# Laser_Teensy4.net
KiCad netlist of a schematic drawn in EAGLE
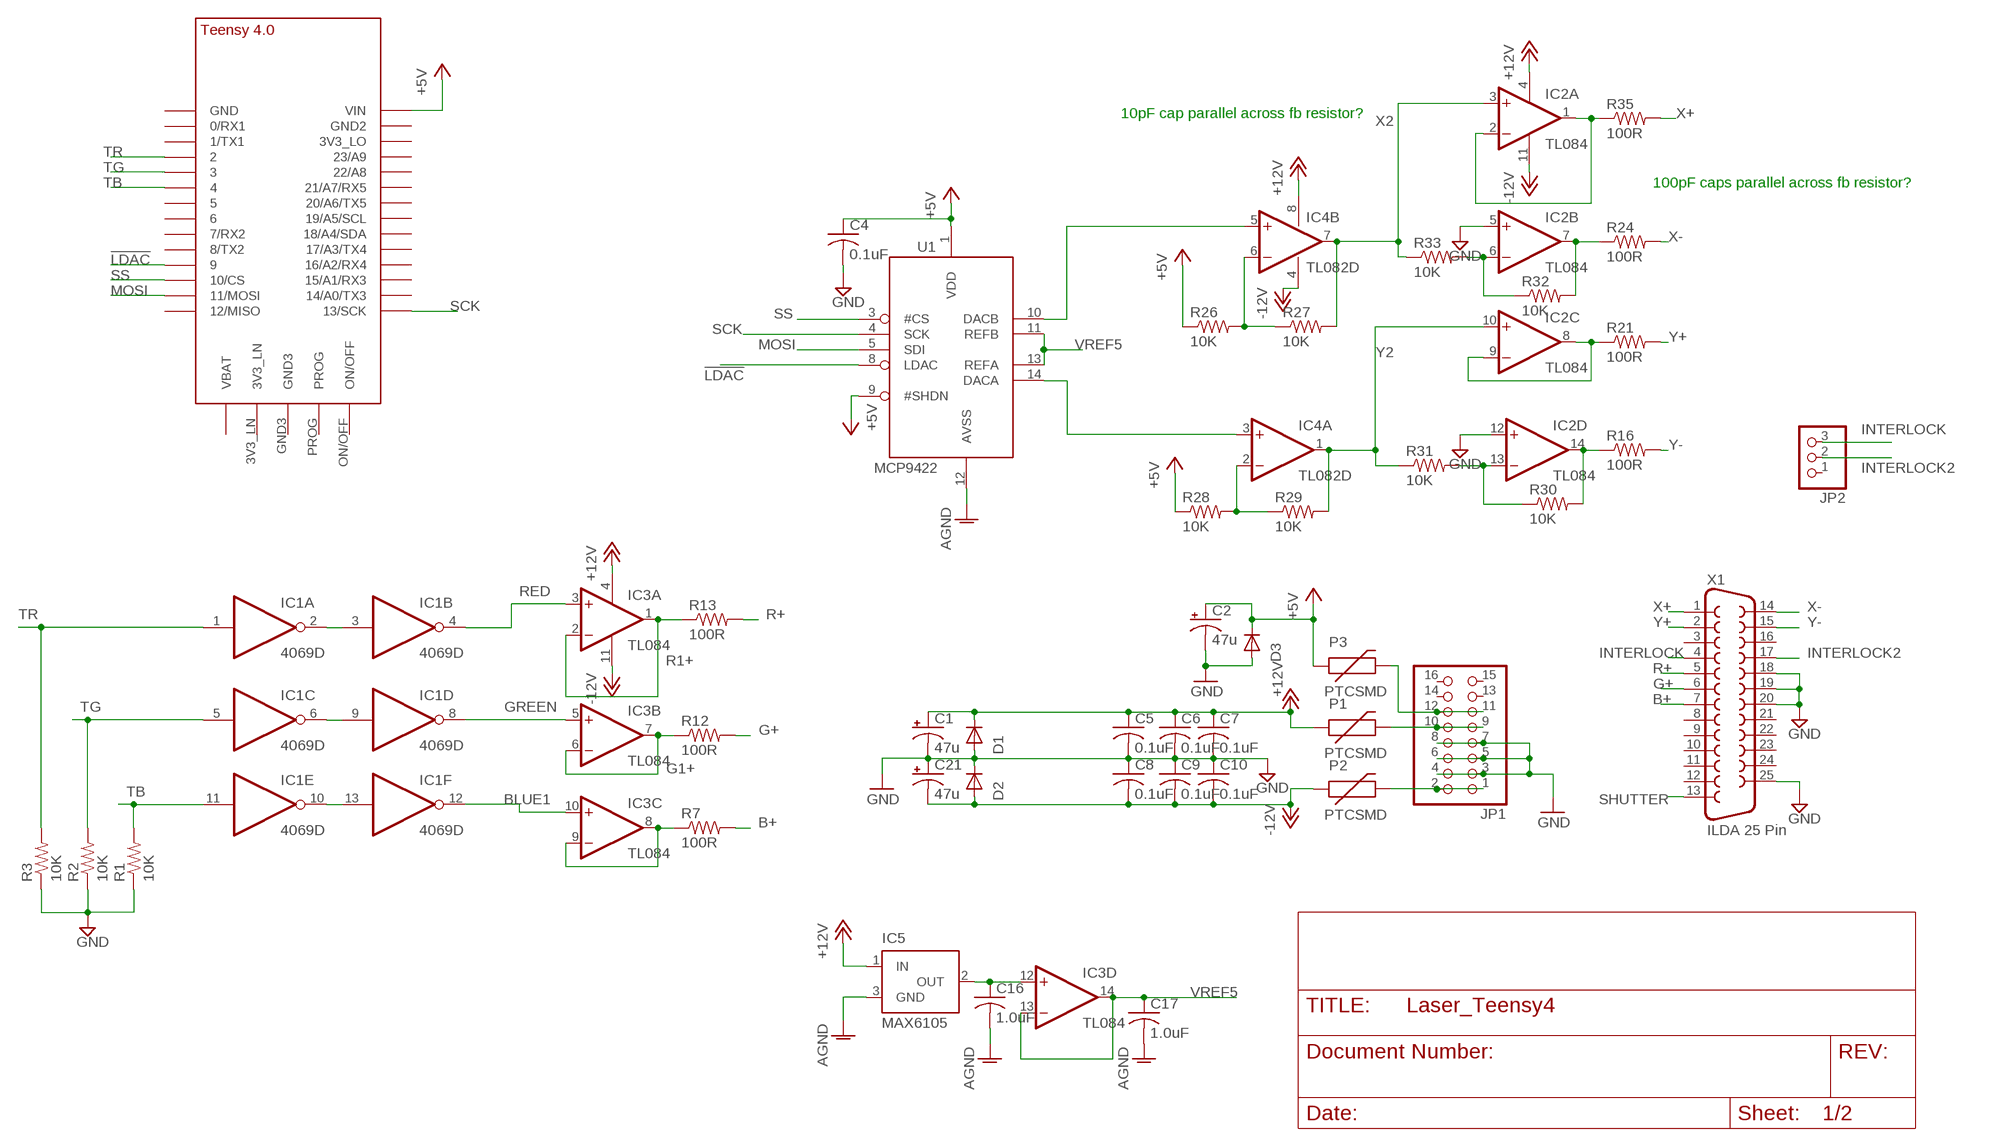
[diagram p0: schematic, sheet 1]
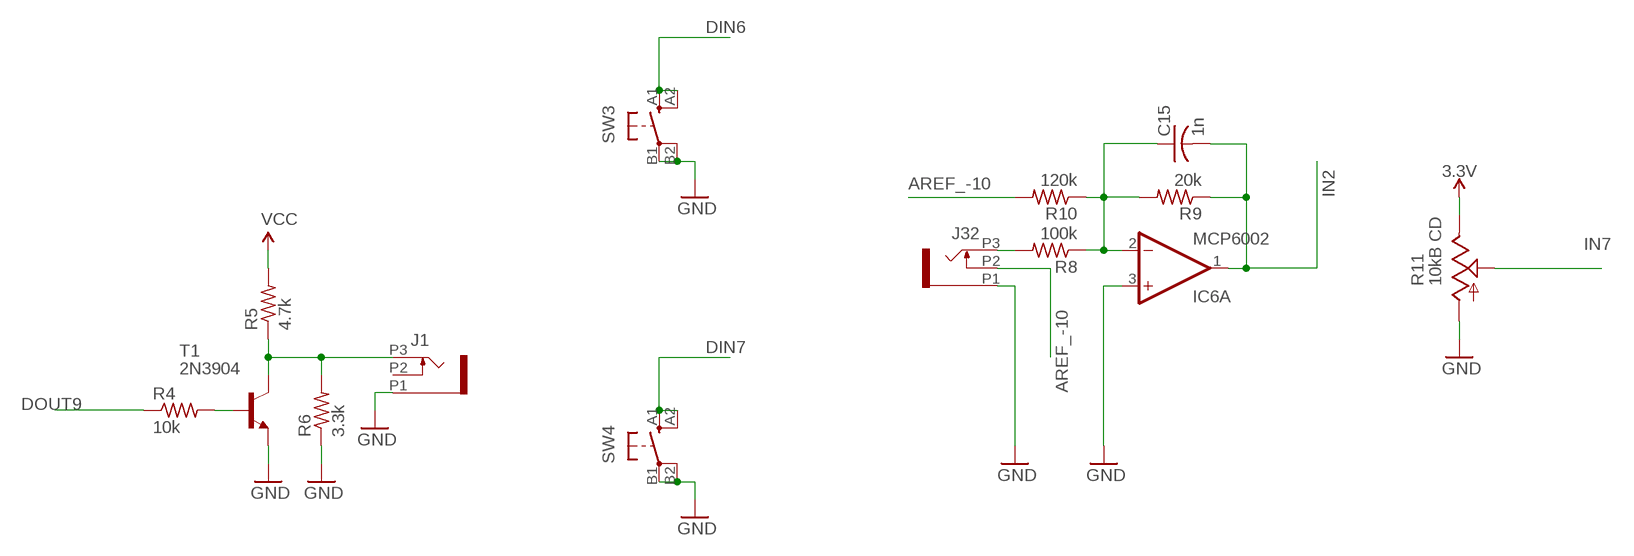
[diagram p1: schematic, sheet 2]

(export (version "E")
  (design (tool "Eeschema 10.0.6"))
  (components
    (comp (ref "C15")
      (value "1n")
      (footprint "eagle-import:C050-025X075")
      (libsource (lib "eagle-import") (part "rcl_334_C-US050-025X075"))
    )
    (comp (ref "IC6")
      (value "MCP6002")
      (footprint "eagle-import:SO08")
      (libsource (lib "eagle-import") (part "TL072D"))
    )
    (comp (ref "J1")
      (value "PJ301_THONKICONN6")
      (footprint "eagle-import:WQP_PJ_301M6")
      (libsource (lib "eagle-import") (part "PJ301_THONKICONN6"))
    )
    (comp (ref "J32")
      (value "PJ301_THONKICONN6")
      (footprint "eagle-import:WQP_PJ_301M6")
      (libsource (lib "eagle-import") (part "PJ301_THONKICONN6"))
    )
    (comp (ref "R4")
      (value "10k")
      (footprint "eagle-import:0204_7")
      (libsource (lib "eagle-import") (part "R-US_0204/7"))
    )
    (comp (ref "R5")
      (value "4.7k")
      (footprint "eagle-import:0204_7")
      (libsource (lib "eagle-import") (part "R-US_0204/7"))
    )
    (comp (ref "R6")
      (value "3.3k")
      (footprint "eagle-import:0204_7")
      (libsource (lib "eagle-import") (part "R-US_0204/7"))
    )
    (comp (ref "R8")
      (value "100k")
      (footprint "eagle-import:0204_7")
      (libsource (lib "eagle-import") (part "R-US_0204/7"))
    )
    (comp (ref "R9")
      (value "20k")
      (footprint "eagle-import:0204_7")
      (libsource (lib "eagle-import") (part "R-US_0204/7"))
    )
    (comp (ref "R10")
      (value "120k")
      (footprint "eagle-import:0204_7")
      (libsource (lib "eagle-import") (part "R-US_0204/7"))
    )
    (comp (ref "R11")
      (value "10kB CD")
      (footprint "eagle-import:ALPS_POT_VERTICAL_PS")
      (libsource (lib "eagle-import") (part "POT_USVERTICAL_PS"))
    )
    (comp (ref "SW3")
      (value "D6R")
      (footprint "eagle-import:D6R")
      (libsource (lib "eagle-import") (part "D6R"))
    )
    (comp (ref "SW4")
      (value "D6R")
      (footprint "eagle-import:D6R")
      (libsource (lib "eagle-import") (part "D6R"))
    )
    (comp (ref "T1")
      (value "2N3904")
      (footprint "eagle-import:TO92")
      (libsource (lib "eagle-import") (part "2N3904"))
    )
    (comp (ref "C1")
      (value "47u")
      (footprint "eagle-import:PANASONIC_D")
      (libsource (lib "eagle-import") (part "CPOL-USD"))
    )
    (comp (ref "C2")
      (value "47u")
      (footprint "eagle-import:PANASONIC_D")
      (libsource (lib "eagle-import") (part "CPOL-USD"))
    )
    (comp (ref "C4")
      (value "0.1uF")
      (footprint "eagle-import:C0603")
      (libsource (lib "eagle-import") (part "C-USC0603"))
    )
    (comp (ref "C5")
      (value "0.1uF")
      (footprint "eagle-import:C0603")
      (libsource (lib "eagle-import") (part "C-USC0603"))
    )
    (comp (ref "C6")
      (value "0.1uF")
      (footprint "eagle-import:C0603")
      (libsource (lib "eagle-import") (part "C-USC0603"))
    )
    (comp (ref "C7")
      (value "0.1uF")
      (footprint "eagle-import:C0603")
      (libsource (lib "eagle-import") (part "C-USC0603"))
    )
    (comp (ref "C8")
      (value "0.1uF")
      (footprint "eagle-import:C0603")
      (libsource (lib "eagle-import") (part "C-USC0603"))
    )
    (comp (ref "C9")
      (value "0.1uF")
      (footprint "eagle-import:C0603")
      (libsource (lib "eagle-import") (part "C-USC0603"))
    )
    (comp (ref "C10")
      (value "0.1uF")
      (footprint "eagle-import:C0603")
      (libsource (lib "eagle-import") (part "C-USC0603"))
    )
    (comp (ref "C16")
      (value "1.0uF")
      (footprint "eagle-import:C025-024X044")
      (libsource (lib "eagle-import") (part "C-US025-024X044"))
    )
    (comp (ref "C17")
      (value "1.0uF")
      (footprint "eagle-import:C025-024X044")
      (libsource (lib "eagle-import") (part "C-US025-024X044"))
    )
    (comp (ref "C21")
      (value "47u")
      (footprint "eagle-import:PANASONIC_D")
      (libsource (lib "eagle-import") (part "CPOL-USD"))
    )
    (comp (ref "D1")
      (value "1N5819HW")
      (footprint "eagle-import:SOD123")
      (libsource (lib "eagle-import") (part "DIODE-SOD123"))
    )
    (comp (ref "D2")
      (value "1N5819HW")
      (footprint "eagle-import:SOD123")
      (libsource (lib "eagle-import") (part "DIODE-SOD123"))
    )
    (comp (ref "D3")
      (value "1N5819HW")
      (footprint "eagle-import:SOD123")
      (libsource (lib "eagle-import") (part "DIODE-SOD123"))
    )
    (comp (ref "IC1")
      (value "4069D")
      (footprint "eagle-import:SO14")
      (libsource (lib "eagle-import") (part "4069D"))
    )
    (comp (ref "IC2")
      (value "TL084")
      (footprint "eagle-import:SOIC-14")
      (libsource (lib "eagle-import") (part "TL084"))
    )
    (comp (ref "IC3")
      (value "TL084")
      (footprint "eagle-import:SOIC-14")
      (libsource (lib "eagle-import") (part "TL084"))
    )
    (comp (ref "IC4")
      (value "TL082D")
      (footprint "eagle-import:SO08")
      (libsource (lib "eagle-import") (part "TL082D"))
    )
    (comp (ref "IC5")
      (value "MAX6105")
      (footprint "eagle-import:SOT23")
      (libsource (lib "eagle-import") (part "MAX6520"))
    )
    (comp (ref "JP1")
      (value "PINHD-2X8")
      (footprint "eagle-import:2X08")
      (libsource (lib "eagle-import") (part "PINHD-2X8"))
    )
    (comp (ref "JP2")
      (value "PINHD-1X3")
      (footprint "eagle-import:1X03")
      (libsource (lib "eagle-import") (part "PINHD-1X3"))
    )
    (comp (ref "P1")
      (value "PTCSMD")
      (footprint "eagle-import:PTC-1206")
      (libsource (lib "eagle-import") (part "PTCSMD"))
    )
    (comp (ref "P2")
      (value "PTCSMD")
      (footprint "eagle-import:PTC-1206")
      (libsource (lib "eagle-import") (part "PTCSMD"))
    )
    (comp (ref "P3")
      (value "PTCSMD")
      (footprint "eagle-import:PTC-1206")
      (libsource (lib "eagle-import") (part "PTCSMD"))
    )
    (comp (ref "R1")
      (value "10K")
      (footprint "eagle-import:R0603")
      (libsource (lib "eagle-import") (part "resistor_R-US_R0603"))
    )
    (comp (ref "R2")
      (value "10K")
      (footprint "eagle-import:R0603")
      (libsource (lib "eagle-import") (part "resistor_R-US_R0603"))
    )
    (comp (ref "R3")
      (value "10K")
      (footprint "eagle-import:R0603")
      (libsource (lib "eagle-import") (part "resistor_R-US_R0603"))
    )
    (comp (ref "R7")
      (value "100R")
      (footprint "eagle-import:R0603")
      (libsource (lib "eagle-import") (part "resistor_R-US_R0603"))
    )
    (comp (ref "R12")
      (value "100R")
      (footprint "eagle-import:R0603")
      (libsource (lib "eagle-import") (part "resistor_R-US_R0603"))
    )
    (comp (ref "R13")
      (value "100R")
      (footprint "eagle-import:R0603")
      (libsource (lib "eagle-import") (part "resistor_R-US_R0603"))
    )
    (comp (ref "R16")
      (value "100R")
      (footprint "eagle-import:R0603")
      (libsource (lib "eagle-import") (part "resistor_R-US_R0603"))
    )
    (comp (ref "R21")
      (value "100R")
      (footprint "eagle-import:R0603")
      (libsource (lib "eagle-import") (part "resistor_R-US_R0603"))
    )
    (comp (ref "R24")
      (value "100R")
      (footprint "eagle-import:R0603")
      (libsource (lib "eagle-import") (part "resistor_R-US_R0603"))
    )
    (comp (ref "R26")
      (value "10K")
      (footprint "eagle-import:R0603")
      (libsource (lib "eagle-import") (part "resistor_R-US_R0603"))
    )
    (comp (ref "R27")
      (value "10K")
      (footprint "eagle-import:R0603")
      (libsource (lib "eagle-import") (part "resistor_R-US_R0603"))
    )
    (comp (ref "R28")
      (value "10K")
      (footprint "eagle-import:R0603")
      (libsource (lib "eagle-import") (part "resistor_R-US_R0603"))
    )
    (comp (ref "R29")
      (value "10K")
      (footprint "eagle-import:R0603")
      (libsource (lib "eagle-import") (part "resistor_R-US_R0603"))
    )
    (comp (ref "R30")
      (value "10K")
      (footprint "eagle-import:R0603")
      (libsource (lib "eagle-import") (part "resistor_R-US_R0603"))
    )
    (comp (ref "R31")
      (value "10K")
      (footprint "eagle-import:R0603")
      (libsource (lib "eagle-import") (part "resistor_R-US_R0603"))
    )
    (comp (ref "R32")
      (value "10K")
      (footprint "eagle-import:R0603")
      (libsource (lib "eagle-import") (part "resistor_R-US_R0603"))
    )
    (comp (ref "R33")
      (value "10K")
      (footprint "eagle-import:R0603")
      (libsource (lib "eagle-import") (part "resistor_R-US_R0603"))
    )
    (comp (ref "R35")
      (value "100R")
      (footprint "eagle-import:R0603")
      (libsource (lib "eagle-import") (part "resistor_R-US_R0603"))
    )
    (comp (ref "U$1")
      (value "TEENSY_4.0")
      (footprint "eagle-import:TEENSY_4.0")
      (libsource (lib "eagle-import") (part "TEENSY_4.0"))
    )
    (comp (ref "U1")
      (value "MCP4922")
      (footprint "eagle-import:SOIC-14")
      (libsource (lib "eagle-import") (part "MCP4922"))
    )
    (comp (ref "X1")
      (value "ILDA 25 Pin")
      (footprint "eagle-import:F25D")
      (libsource (lib "eagle-import") (part "F25D"))
    )
  )
  (nets
    (net (code "1") (name "+5V") (class "Default")
      (node (ref "C2") (pin "+") (pinfunction "+_+") (pintype "passive"))
      (node (ref "C4") (pin "1") (pinfunction "1_1") (pintype "passive"))
      (node (ref "D3") (pin "C") (pinfunction "C_C") (pintype "passive"))
      (node (ref "P3") (pin "1") (pinfunction "1_1") (pintype "bidirectional"))
      (node (ref "R26") (pin "1") (pinfunction "1_1") (pintype "passive"))
      (node (ref "R28") (pin "1") (pinfunction "1_1") (pintype "passive"))
      (node (ref "U$1") (pin "VIN") (pinfunction "VIN_VIN") (pintype "bidirectional"))
      (node (ref "U1") (pin "1") (pinfunction "VDD_1") (pintype "power_in"))
      (node (ref "U1") (pin "9") (pinfunction "#SHDN_9") (pintype "input"))
    )
    (net (code "2") (name "+12V") (class "Default")
      (node (ref "C1") (pin "+") (pinfunction "+_+") (pintype "passive"))
      (node (ref "C5") (pin "1") (pinfunction "1_1") (pintype "passive"))
      (node (ref "C6") (pin "1") (pinfunction "1_1") (pintype "passive"))
      (node (ref "C7") (pin "1") (pinfunction "1_1") (pintype "passive"))
      (node (ref "D1") (pin "C") (pinfunction "C_C") (pintype "passive"))
      (node (ref "IC2") (pin "4") (pinfunction "V+_4") (pintype "power_in"))
      (node (ref "IC3") (pin "4") (pinfunction "V+_4") (pintype "power_in"))
      (node (ref "IC4") (pin "8") (pinfunction "V+_8") (pintype "power_in"))
      (node (ref "IC5") (pin "1") (pinfunction "IN_1") (pintype "input"))
      (node (ref "P1") (pin "1") (pinfunction "1_1") (pintype "bidirectional"))
    )
    (net (code "3") (name "-12V") (class "Default")
      (node (ref "C10") (pin "2") (pinfunction "2_2") (pintype "passive"))
      (node (ref "C21") (pin "-") (pinfunction "-_-") (pintype "passive"))
      (node (ref "C8") (pin "2") (pinfunction "2_2") (pintype "passive"))
      (node (ref "C9") (pin "2") (pinfunction "2_2") (pintype "passive"))
      (node (ref "D2") (pin "A") (pinfunction "A_A") (pintype "passive"))
      (node (ref "IC2") (pin "11") (pinfunction "V-_11") (pintype "power_in"))
      (node (ref "IC3") (pin "11") (pinfunction "V-_11") (pintype "power_in"))
      (node (ref "IC4") (pin "4") (pinfunction "V-_4") (pintype "power_in"))
      (node (ref "P2") (pin "1") (pinfunction "1_1") (pintype "bidirectional"))
    )
    (net (code "4") (name "3.3V") (class "Default")
      (node (ref "R11") (pin "P$1") (pinfunction "E_P$1") (pintype "passive"))
    )
    (net (code "5") (name "AGND") (class "Default")
      (node (ref "C16") (pin "2") (pinfunction "2_2") (pintype "passive"))
      (node (ref "C17") (pin "2") (pinfunction "2_2") (pintype "passive"))
      (node (ref "IC5") (pin "3") (pinfunction "GND_3") (pintype "power_in"))
      (node (ref "U1") (pin "12") (pinfunction "AVSS_12") (pintype "power_in"))
    )
    (net (code "6") (name "AREF_-10") (class "Default")
      (node (ref "J32") (pin "P2") (pinfunction "2_P2") (pintype "passive"))
      (node (ref "R10") (pin "2") (pinfunction "2_2") (pintype "passive"))
    )
    (net (code "7") (name "B+") (class "Default")
      (node (ref "R7") (pin "2") (pinfunction "2_2") (pintype "passive"))
      (node (ref "X1") (pin "7") (pinfunction "7_7") (pintype "passive"))
    )
    (net (code "8") (name "BLUE1") (class "Default")
      (node (ref "IC1") (pin "12") (pinfunction "O_12") (pintype "output"))
      (node (ref "IC3") (pin "10") (pinfunction "+IN_10") (pintype "input"))
    )
    (net (code "9") (name "DIN6") (class "Default")
      (node (ref "SW3") (pin "A1") (pinfunction "S_A1") (pintype "passive"))
      (node (ref "SW3") (pin "A2") (pinfunction "S1_A2") (pintype "passive"))
    )
    (net (code "10") (name "DIN7") (class "Default")
      (node (ref "SW4") (pin "A1") (pinfunction "S_A1") (pintype "passive"))
      (node (ref "SW4") (pin "A2") (pinfunction "S1_A2") (pintype "passive"))
    )
    (net (code "11") (name "DOUT9") (class "Default")
      (node (ref "R4") (pin "1") (pinfunction "1_1") (pintype "passive"))
    )
    (net (code "12") (name "G+") (class "Default")
      (node (ref "R12") (pin "2") (pinfunction "2_2") (pintype "passive"))
      (node (ref "X1") (pin "6") (pinfunction "6_6") (pintype "passive"))
    )
    (net (code "13") (name "G1+") (class "Default")
      (node (ref "IC3") (pin "6") (pinfunction "-IN_6") (pintype "input"))
      (node (ref "IC3") (pin "7") (pinfunction "OUT_7") (pintype "output"))
      (node (ref "R12") (pin "1") (pinfunction "1_1") (pintype "passive"))
    )
    (net (code "14") (name "GND") (class "Default")
      (node (ref "C1") (pin "-") (pinfunction "-_-") (pintype "passive"))
      (node (ref "C10") (pin "1") (pinfunction "1_1") (pintype "passive"))
      (node (ref "C2") (pin "-") (pinfunction "-_-") (pintype "passive"))
      (node (ref "C21") (pin "+") (pinfunction "+_+") (pintype "passive"))
      (node (ref "C4") (pin "2") (pinfunction "2_2") (pintype "passive"))
      (node (ref "C5") (pin "2") (pinfunction "2_2") (pintype "passive"))
      (node (ref "C6") (pin "2") (pinfunction "2_2") (pintype "passive"))
      (node (ref "C7") (pin "2") (pinfunction "2_2") (pintype "passive"))
      (node (ref "C8") (pin "1") (pinfunction "1_1") (pintype "passive"))
      (node (ref "C9") (pin "1") (pinfunction "1_1") (pintype "passive"))
      (node (ref "D1") (pin "A") (pinfunction "A_A") (pintype "passive"))
      (node (ref "D2") (pin "C") (pinfunction "C_C") (pintype "passive"))
      (node (ref "D3") (pin "A") (pinfunction "A_A") (pintype "passive"))
      (node (ref "IC2") (pin "12") (pinfunction "+IN_12") (pintype "input"))
      (node (ref "IC2") (pin "5") (pinfunction "+IN_5") (pintype "input"))
      (node (ref "IC6") (pin "3") (pinfunction "+IN_3") (pintype "input"))
      (node (ref "J1") (pin "P1") (pinfunction "1_P1") (pintype "passive"))
      (node (ref "J32") (pin "P1") (pinfunction "1_P1") (pintype "passive"))
      (node (ref "JP1") (pin "3") (pinfunction "3_3") (pintype "passive"))
      (node (ref "JP1") (pin "4") (pinfunction "4_4") (pintype "passive"))
      (node (ref "JP1") (pin "5") (pinfunction "5_5") (pintype "passive"))
      (node (ref "JP1") (pin "6") (pinfunction "6_6") (pintype "passive"))
      (node (ref "JP1") (pin "7") (pinfunction "7_7") (pintype "passive"))
      (node (ref "JP1") (pin "8") (pinfunction "8_8") (pintype "passive"))
      (node (ref "R1") (pin "1") (pinfunction "1_1") (pintype "passive"))
      (node (ref "R11") (pin "P$3") (pinfunction "A_P$3") (pintype "passive"))
      (node (ref "R2") (pin "1") (pinfunction "1_1") (pintype "passive"))
      (node (ref "R3") (pin "1") (pinfunction "1_1") (pintype "passive"))
      (node (ref "R6") (pin "1") (pinfunction "1_1") (pintype "passive"))
      (node (ref "SW3") (pin "B1") (pinfunction "P_B1") (pintype "passive"))
      (node (ref "SW3") (pin "B2") (pinfunction "P1_B2") (pintype "passive"))
      (node (ref "SW4") (pin "B1") (pinfunction "P_B1") (pintype "passive"))
      (node (ref "SW4") (pin "B2") (pinfunction "P1_B2") (pintype "passive"))
      (node (ref "T1") (pin "3") (pinfunction "E_3") (pintype "passive"))
      (node (ref "X1") (pin "18") (pinfunction "18_18") (pintype "passive"))
      (node (ref "X1") (pin "19") (pinfunction "19_19") (pintype "passive"))
      (node (ref "X1") (pin "20") (pinfunction "20_20") (pintype "passive"))
      (node (ref "X1") (pin "25") (pinfunction "25_25") (pintype "passive"))
    )
    (net (code "15") (name "GREEN") (class "Default")
      (node (ref "IC1") (pin "8") (pinfunction "O_8") (pintype "output"))
      (node (ref "IC3") (pin "5") (pinfunction "+IN_5") (pintype "input"))
    )
    (net (code "16") (name "IN2") (class "Default")
      (node (ref "C15") (pin "2") (pinfunction "2_2") (pintype "passive"))
      (node (ref "IC6") (pin "1") (pinfunction "OUT_1") (pintype "output"))
      (node (ref "R9") (pin "1") (pinfunction "1_1") (pintype "passive"))
    )
    (net (code "17") (name "IN7") (class "Default")
      (node (ref "R11") (pin "P$2") (pinfunction "S_P$2") (pintype "passive"))
    )
    (net (code "18") (name "INTERLOCK") (class "Default")
      (node (ref "JP2") (pin "3") (pinfunction "3_3") (pintype "passive"))
      (node (ref "X1") (pin "4") (pinfunction "4_4") (pintype "passive"))
    )
    (net (code "19") (name "INTERLOCK2") (class "Default")
      (node (ref "JP2") (pin "2") (pinfunction "2_2") (pintype "passive"))
      (node (ref "X1") (pin "17") (pinfunction "17_17") (pintype "passive"))
    )
    (net (code "20") (name "MOSI") (class "Default")
      (node (ref "U$1") (pin "11/MOSI") (pinfunction "11/MOSI_11/MOSI") (pintype "bidirectional"))
      (node (ref "U1") (pin "5") (pinfunction "SDI_5") (pintype "input"))
    )
    (net (code "21") (name "Net-(IC1A-O)") (class "Default")
      (node (ref "IC1") (pin "2") (pinfunction "O_2") (pintype "output"))
      (node (ref "IC1") (pin "3") (pinfunction "I_3") (pintype "input"))
    )
    (net (code "22") (name "Net-(IC1C-O)") (class "Default")
      (node (ref "IC1") (pin "6") (pinfunction "O_6") (pintype "output"))
      (node (ref "IC1") (pin "9") (pinfunction "I_9") (pintype "input"))
    )
    (net (code "23") (name "Net-(IC1E-O)") (class "Default")
      (node (ref "IC1") (pin "10") (pinfunction "O_10") (pintype "output"))
      (node (ref "IC1") (pin "13") (pinfunction "I_13") (pintype "input"))
    )
    (net (code "24") (name "Net-(IC2A--IN)") (class "Default")
      (node (ref "IC2") (pin "1") (pinfunction "OUT_1") (pintype "output"))
      (node (ref "IC2") (pin "2") (pinfunction "-IN_2") (pintype "input"))
      (node (ref "R35") (pin "1") (pinfunction "1_1") (pintype "passive"))
    )
    (net (code "25") (name "Net-(IC2B--IN)") (class "Default")
      (node (ref "IC2") (pin "6") (pinfunction "-IN_6") (pintype "input"))
      (node (ref "R32") (pin "1") (pinfunction "1_1") (pintype "passive"))
      (node (ref "R33") (pin "2") (pinfunction "2_2") (pintype "passive"))
    )
    (net (code "26") (name "Net-(IC2B-OUT)") (class "Default")
      (node (ref "IC2") (pin "7") (pinfunction "OUT_7") (pintype "output"))
      (node (ref "R24") (pin "1") (pinfunction "1_1") (pintype "passive"))
      (node (ref "R32") (pin "2") (pinfunction "2_2") (pintype "passive"))
    )
    (net (code "27") (name "Net-(IC2C--IN)") (class "Default")
      (node (ref "IC2") (pin "8") (pinfunction "OUT_8") (pintype "output"))
      (node (ref "IC2") (pin "9") (pinfunction "-IN_9") (pintype "input"))
      (node (ref "R21") (pin "1") (pinfunction "1_1") (pintype "passive"))
    )
    (net (code "28") (name "Net-(IC2D--IN)") (class "Default")
      (node (ref "IC2") (pin "13") (pinfunction "-IN_13") (pintype "input"))
      (node (ref "R30") (pin "1") (pinfunction "1_1") (pintype "passive"))
      (node (ref "R31") (pin "2") (pinfunction "2_2") (pintype "passive"))
    )
    (net (code "29") (name "Net-(IC2D-OUT)") (class "Default")
      (node (ref "IC2") (pin "14") (pinfunction "OUT_14") (pintype "output"))
      (node (ref "R16") (pin "1") (pinfunction "1_1") (pintype "passive"))
      (node (ref "R30") (pin "2") (pinfunction "2_2") (pintype "passive"))
    )
    (net (code "30") (name "Net-(IC3C--IN)") (class "Default")
      (node (ref "IC3") (pin "8") (pinfunction "OUT_8") (pintype "output"))
      (node (ref "IC3") (pin "9") (pinfunction "-IN_9") (pintype "input"))
      (node (ref "R7") (pin "1") (pinfunction "1_1") (pintype "passive"))
    )
    (net (code "31") (name "Net-(IC3D-+IN)") (class "Default")
      (node (ref "C16") (pin "1") (pinfunction "1_1") (pintype "passive"))
      (node (ref "IC3") (pin "12") (pinfunction "+IN_12") (pintype "input"))
      (node (ref "IC5") (pin "2") (pinfunction "OUT_2") (pintype "input"))
    )
    (net (code "32") (name "Net-(IC4A-+IN)") (class "Default")
      (node (ref "IC4") (pin "3") (pinfunction "+IN_3") (pintype "input"))
      (node (ref "U1") (pin "14") (pinfunction "DACA_14") (pintype "output"))
    )
    (net (code "33") (name "Net-(IC4A--IN)") (class "Default")
      (node (ref "IC4") (pin "2") (pinfunction "-IN_2") (pintype "input"))
      (node (ref "R28") (pin "2") (pinfunction "2_2") (pintype "passive"))
      (node (ref "R29") (pin "1") (pinfunction "1_1") (pintype "passive"))
    )
    (net (code "34") (name "Net-(IC4B-+IN)") (class "Default")
      (node (ref "IC4") (pin "5") (pinfunction "+IN_5") (pintype "input"))
      (node (ref "U1") (pin "10") (pinfunction "DACB_10") (pintype "output"))
    )
    (net (code "35") (name "Net-(IC4B--IN)") (class "Default")
      (node (ref "IC4") (pin "6") (pinfunction "-IN_6") (pintype "input"))
      (node (ref "R26") (pin "2") (pinfunction "2_2") (pintype "passive"))
      (node (ref "R27") (pin "1") (pinfunction "1_1") (pintype "passive"))
    )
    (net (code "36") (name "Net-(IC6A--IN)") (class "Default")
      (node (ref "C15") (pin "1") (pinfunction "1_1") (pintype "passive"))
      (node (ref "IC6") (pin "2") (pinfunction "-IN_2") (pintype "input"))
      (node (ref "R10") (pin "1") (pinfunction "1_1") (pintype "passive"))
      (node (ref "R8") (pin "1") (pinfunction "1_1") (pintype "passive"))
      (node (ref "R9") (pin "2") (pinfunction "2_2") (pintype "passive"))
    )
    (net (code "37") (name "Net-(J1-3)") (class "Default")
      (node (ref "J1") (pin "P3") (pinfunction "3_P3") (pintype "passive"))
      (node (ref "R5") (pin "1") (pinfunction "1_1") (pintype "passive"))
      (node (ref "R6") (pin "2") (pinfunction "2_2") (pintype "passive"))
      (node (ref "T1") (pin "1") (pinfunction "C_1") (pintype "passive"))
    )
    (net (code "38") (name "Net-(J32-3)") (class "Default")
      (node (ref "J32") (pin "P3") (pinfunction "3_P3") (pintype "passive"))
      (node (ref "R8") (pin "2") (pinfunction "2_2") (pintype "passive"))
    )
    (net (code "39") (name "Net-(JP1-Pad1)") (class "Default")
      (node (ref "JP1") (pin "1") (pinfunction "1_1") (pintype "passive"))
      (node (ref "JP1") (pin "2") (pinfunction "2_2") (pintype "passive"))
      (node (ref "P2") (pin "2") (pinfunction "2_2") (pintype "bidirectional"))
    )
    (net (code "40") (name "Net-(JP1-Pad10)") (class "Default")
      (node (ref "JP1") (pin "10") (pinfunction "10_10") (pintype "passive"))
      (node (ref "JP1") (pin "9") (pinfunction "9_9") (pintype "passive"))
      (node (ref "P1") (pin "2") (pinfunction "2_2") (pintype "bidirectional"))
    )
    (net (code "41") (name "Net-(JP1-Pad11)") (class "Default")
      (node (ref "JP1") (pin "11") (pinfunction "11_11") (pintype "passive"))
      (node (ref "JP1") (pin "12") (pinfunction "12_12") (pintype "passive"))
      (node (ref "P3") (pin "2") (pinfunction "2_2") (pintype "bidirectional"))
    )
    (net (code "42") (name "Net-(T1-B)") (class "Default")
      (node (ref "R4") (pin "2") (pinfunction "2_2") (pintype "passive"))
      (node (ref "T1") (pin "2") (pinfunction "B_2") (pintype "passive"))
    )
    (net (code "43") (name "R+") (class "Default")
      (node (ref "R13") (pin "2") (pinfunction "2_2") (pintype "passive"))
      (node (ref "X1") (pin "5") (pinfunction "5_5") (pintype "passive"))
    )
    (net (code "44") (name "R1+") (class "Default")
      (node (ref "IC3") (pin "1") (pinfunction "OUT_1") (pintype "output"))
      (node (ref "IC3") (pin "2") (pinfunction "-IN_2") (pintype "input"))
      (node (ref "R13") (pin "1") (pinfunction "1_1") (pintype "passive"))
    )
    (net (code "45") (name "RED") (class "Default")
      (node (ref "IC1") (pin "4") (pinfunction "O_4") (pintype "output"))
      (node (ref "IC3") (pin "3") (pinfunction "+IN_3") (pintype "input"))
    )
    (net (code "46") (name "SCK") (class "Default")
      (node (ref "U$1") (pin "13/SCK") (pinfunction "13/SCK_13/SCK") (pintype "bidirectional"))
      (node (ref "U1") (pin "4") (pinfunction "SCK_4") (pintype "input"))
    )
    (net (code "47") (name "SHUTTER") (class "Default")
      (node (ref "X1") (pin "13") (pinfunction "13_13") (pintype "passive"))
    )
    (net (code "48") (name "SS") (class "Default")
      (node (ref "U$1") (pin "10/CS") (pinfunction "10/CS_10/CS") (pintype "bidirectional"))
      (node (ref "U1") (pin "3") (pinfunction "#CS_3") (pintype "input"))
    )
    (net (code "49") (name "TB") (class "Default")
      (node (ref "IC1") (pin "11") (pinfunction "I_11") (pintype "input"))
      (node (ref "R1") (pin "2") (pinfunction "2_2") (pintype "passive"))
      (node (ref "U$1") (pin "4/CANRX") (pinfunction "4_4/CANRX") (pintype "bidirectional"))
    )
    (net (code "50") (name "TG") (class "Default")
      (node (ref "IC1") (pin "5") (pinfunction "I_5") (pintype "input"))
      (node (ref "R2") (pin "2") (pinfunction "2_2") (pintype "passive"))
      (node (ref "U$1") (pin "3/CANTX") (pinfunction "3_3/CANTX") (pintype "bidirectional"))
    )
    (net (code "51") (name "TR") (class "Default")
      (node (ref "IC1") (pin "1") (pinfunction "I_1") (pintype "input"))
      (node (ref "R3") (pin "2") (pinfunction "2_2") (pintype "passive"))
      (node (ref "U$1") (pin "2") (pinfunction "2_2") (pintype "bidirectional"))
    )
    (net (code "52") (name "VCC") (class "Default")
      (node (ref "R5") (pin "2") (pinfunction "2_2") (pintype "passive"))
    )
    (net (code "53") (name "VREF5") (class "Default")
      (node (ref "C17") (pin "1") (pinfunction "1_1") (pintype "passive"))
      (node (ref "IC3") (pin "13") (pinfunction "-IN_13") (pintype "input"))
      (node (ref "IC3") (pin "14") (pinfunction "OUT_14") (pintype "output"))
      (node (ref "U1") (pin "11") (pinfunction "REFB_11") (pintype "input"))
      (node (ref "U1") (pin "13") (pinfunction "REFA_13") (pintype "input"))
    )
    (net (code "54") (name "X+") (class "Default")
      (node (ref "R35") (pin "2") (pinfunction "2_2") (pintype "passive"))
      (node (ref "X1") (pin "1") (pinfunction "1_1") (pintype "passive"))
    )
    (net (code "55") (name "X-") (class "Default")
      (node (ref "R24") (pin "2") (pinfunction "2_2") (pintype "passive"))
      (node (ref "X1") (pin "14") (pinfunction "14_14") (pintype "passive"))
    )
    (net (code "56") (name "X2") (class "Default")
      (node (ref "IC2") (pin "3") (pinfunction "+IN_3") (pintype "input"))
      (node (ref "IC4") (pin "7") (pinfunction "OUT_7") (pintype "output"))
      (node (ref "R27") (pin "2") (pinfunction "2_2") (pintype "passive"))
      (node (ref "R33") (pin "1") (pinfunction "1_1") (pintype "passive"))
    )
    (net (code "57") (name "Y+") (class "Default")
      (node (ref "R21") (pin "2") (pinfunction "2_2") (pintype "passive"))
      (node (ref "X1") (pin "2") (pinfunction "2_2") (pintype "passive"))
    )
    (net (code "58") (name "Y-") (class "Default")
      (node (ref "R16") (pin "2") (pinfunction "2_2") (pintype "passive"))
      (node (ref "X1") (pin "15") (pinfunction "15_15") (pintype "passive"))
    )
    (net (code "59") (name "Y2") (class "Default")
      (node (ref "IC2") (pin "10") (pinfunction "+IN_10") (pintype "input"))
      (node (ref "IC4") (pin "1") (pinfunction "OUT_1") (pintype "output"))
      (node (ref "R29") (pin "2") (pinfunction "2_2") (pintype "passive"))
      (node (ref "R31") (pin "1") (pinfunction "1_1") (pintype "passive"))
    )
    (net (code "60") (name "unconnected-(J1-2-PadP2)") (class "Default")
      (node (ref "J1") (pin "P2") (pinfunction "2_P2") (pintype "passive"))
    )
    (net (code "61") (name "unconnected-(JP1-Pad13)") (class "Default")
      (node (ref "JP1") (pin "13") (pinfunction "13_13") (pintype "passive"))
    )
    (net (code "62") (name "unconnected-(JP1-Pad14)") (class "Default")
      (node (ref "JP1") (pin "14") (pinfunction "14_14") (pintype "passive"))
    )
    (net (code "63") (name "unconnected-(JP1-Pad15)") (class "Default")
      (node (ref "JP1") (pin "15") (pinfunction "15_15") (pintype "passive"))
    )
    (net (code "64") (name "unconnected-(JP1-Pad16)") (class "Default")
      (node (ref "JP1") (pin "16") (pinfunction "16_16") (pintype "passive"))
    )
    (net (code "65") (name "unconnected-(JP2-Pad1)") (class "Default")
      (node (ref "JP2") (pin "1") (pinfunction "1_1") (pintype "passive"))
    )
    (net (code "66") (name "unconnected-(U$1-0{slash}RX1-Pad0{slash}RX)") (class "Default")
      (node (ref "U$1") (pin "0/RX") (pinfunction "0/RX1_0/RX") (pintype "bidirectional"))
    )
    (net (code "67") (name "unconnected-(U$1-1{slash}TX1-Pad1{slash}TX)") (class "Default")
      (node (ref "U$1") (pin "1/TX") (pinfunction "1/TX1_1/TX") (pintype "bidirectional"))
    )
    (net (code "68") (name "unconnected-(U$1-7{slash}RX2-Pad7)") (class "Default")
      (node (ref "U$1") (pin "7") (pinfunction "7/RX2_7") (pintype "bidirectional"))
    )
    (net (code "69") (name "unconnected-(U$1-8{slash}TX2-Pad8)") (class "Default")
      (node (ref "U$1") (pin "8") (pinfunction "8/TX2_8") (pintype "bidirectional"))
    )
    (net (code "70") (name "unconnected-(U$1-14{slash}A0{slash}TX3-Pad14{slash}A0)") (class "Default")
      (node (ref "U$1") (pin "14/A0") (pinfunction "14/A0/TX3_14/A0") (pintype "bidirectional"))
    )
    (net (code "71") (name "unconnected-(U$1-15{slash}A1{slash}RX3-Pad15{slash}A1)") (class "Default")
      (node (ref "U$1") (pin "15/A1") (pinfunction "15/A1/RX3_15/A1") (pintype "bidirectional"))
    )
    (net (code "72") (name "unconnected-(U$1-16{slash}A2{slash}RX4-Pad16{slash}A2)") (class "Default")
      (node (ref "U$1") (pin "16/A2") (pinfunction "16/A2/RX4_16/A2") (pintype "bidirectional"))
    )
    (net (code "73") (name "unconnected-(U$1-17{slash}A3{slash}TX4-Pad17{slash}A3)") (class "Default")
      (node (ref "U$1") (pin "17/A3") (pinfunction "17/A3/TX4_17/A3") (pintype "bidirectional"))
    )
    (net (code "74") (name "unconnected-(U$1-20{slash}A6{slash}TX5-Pad20{slash}A6)") (class "Default")
      (node (ref "U$1") (pin "20/A6") (pinfunction "20/A6/TX5_20/A6") (pintype "bidirectional"))
    )
    (net (code "75") (name "unconnected-(U$1-21{slash}A7{slash}RX5-Pad21{slash}A7)") (class "Default")
      (node (ref "U$1") (pin "21/A7") (pinfunction "21/A7/RX5_21/A7") (pintype "bidirectional"))
    )
    (net (code "76") (name "unconnected-(U$1-Pad3V3_LN)") (class "Default")
      (node (ref "U$1") (pin "3V3_LN") (pinfunction "3V3_LN_3V3_LN") (pintype "bidirectional"))
    )
    (net (code "77") (name "unconnected-(U$1-Pad3V3_LO)") (class "Default")
      (node (ref "U$1") (pin "3V3_LO") (pinfunction "3V3_LO_3V3_LO") (pintype "bidirectional"))
    )
    (net (code "78") (name "unconnected-(U$1-Pad5)") (class "Default")
      (node (ref "U$1") (pin "5") (pinfunction "5_5") (pintype "bidirectional"))
    )
    (net (code "79") (name "unconnected-(U$1-Pad6)") (class "Default")
      (node (ref "U$1") (pin "6") (pinfunction "6_6") (pintype "bidirectional"))
    )
    (net (code "80") (name "unconnected-(U$1-Pad12{slash}MISO)") (class "Default")
      (node (ref "U$1") (pin "12/MISO") (pinfunction "12/MISO_12/MISO") (pintype "bidirectional"))
    )
    (net (code "81") (name "unconnected-(U$1-Pad18{slash}A4{slash}SDA)") (class "Default")
      (node (ref "U$1") (pin "18/A4/SDA") (pinfunction "18/A4/SDA_18/A4/SDA") (pintype "bidirectional"))
    )
    (net (code "82") (name "unconnected-(U$1-Pad19{slash}A5{slash}SCL)") (class "Default")
      (node (ref "U$1") (pin "19/A5/SCL") (pinfunction "19/A5/SCL_19/A5/SCL") (pintype "bidirectional"))
    )
    (net (code "83") (name "unconnected-(U$1-Pad22{slash}A8)") (class "Default")
      (node (ref "U$1") (pin "22/A8") (pinfunction "22/A8_22/A8") (pintype "bidirectional"))
    )
    (net (code "84") (name "unconnected-(U$1-Pad23{slash}A9)") (class "Default")
      (node (ref "U$1") (pin "23/A9") (pinfunction "23/A9_23/A9") (pintype "bidirectional"))
    )
    (net (code "85") (name "unconnected-(U$1-PadGND)") (class "Default")
      (node (ref "U$1") (pin "GND") (pinfunction "GND_GND") (pintype "bidirectional"))
    )
    (net (code "86") (name "unconnected-(U$1-PadGND2)") (class "Default")
      (node (ref "U$1") (pin "GND2") (pinfunction "GND2_GND2") (pintype "bidirectional"))
    )
    (net (code "87") (name "unconnected-(U$1-PadGND3)") (class "Default")
      (node (ref "U$1") (pin "GND3") (pinfunction "GND3_GND3") (pintype "bidirectional"))
    )
    (net (code "88") (name "unconnected-(U$1-PadON{slash}OFF)") (class "Default")
      (node (ref "U$1") (pin "ON/OFF") (pinfunction "ON/OFF_ON/OFF") (pintype "bidirectional"))
    )
    (net (code "89") (name "unconnected-(U$1-PadPROG)") (class "Default")
      (node (ref "U$1") (pin "PROG") (pinfunction "PROG_PROG") (pintype "bidirectional"))
    )
    (net (code "90") (name "unconnected-(U$1-VBAT-PadVBAT\\)") (class "Default")
      (node (ref "U$1") (pin "VBAT\\") (pinfunction "VBAT_VBAT\\") (pintype "bidirectional"))
    )
    (net (code "91") (name "unconnected-(X1-Pad3)") (class "Default")
      (node (ref "X1") (pin "3") (pinfunction "3_3") (pintype "passive"))
    )
    (net (code "92") (name "unconnected-(X1-Pad8)") (class "Default")
      (node (ref "X1") (pin "8") (pinfunction "8_8") (pintype "passive"))
    )
    (net (code "93") (name "unconnected-(X1-Pad9)") (class "Default")
      (node (ref "X1") (pin "9") (pinfunction "9_9") (pintype "passive"))
    )
    (net (code "94") (name "unconnected-(X1-Pad10)") (class "Default")
      (node (ref "X1") (pin "10") (pinfunction "10_10") (pintype "passive"))
    )
    (net (code "95") (name "unconnected-(X1-Pad11)") (class "Default")
      (node (ref "X1") (pin "11") (pinfunction "11_11") (pintype "passive"))
    )
    (net (code "96") (name "unconnected-(X1-Pad12)") (class "Default")
      (node (ref "X1") (pin "12") (pinfunction "12_12") (pintype "passive"))
    )
    (net (code "97") (name "unconnected-(X1-Pad16)") (class "Default")
      (node (ref "X1") (pin "16") (pinfunction "16_16") (pintype "passive"))
    )
    (net (code "98") (name "unconnected-(X1-Pad21)") (class "Default")
      (node (ref "X1") (pin "21") (pinfunction "21_21") (pintype "passive"))
    )
    (net (code "99") (name "unconnected-(X1-Pad22)") (class "Default")
      (node (ref "X1") (pin "22") (pinfunction "22_22") (pintype "passive"))
    )
    (net (code "100") (name "unconnected-(X1-Pad23)") (class "Default")
      (node (ref "X1") (pin "23") (pinfunction "23_23") (pintype "passive"))
    )
    (net (code "101") (name "unconnected-(X1-Pad24)") (class "Default")
      (node (ref "X1") (pin "24") (pinfunction "24_24") (pintype "passive"))
    )
    (net (code "102") (name "~{LDAC}") (class "Default")
      (node (ref "U$1") (pin "9/CS") (pinfunction "9_9/CS") (pintype "bidirectional"))
      (node (ref "U1") (pin "8") (pinfunction "LDAC_8") (pintype "input"))
    )
  )
)
